# Driver_Motor.net
KiCad netlist of a schematic drawn in Altium Designer
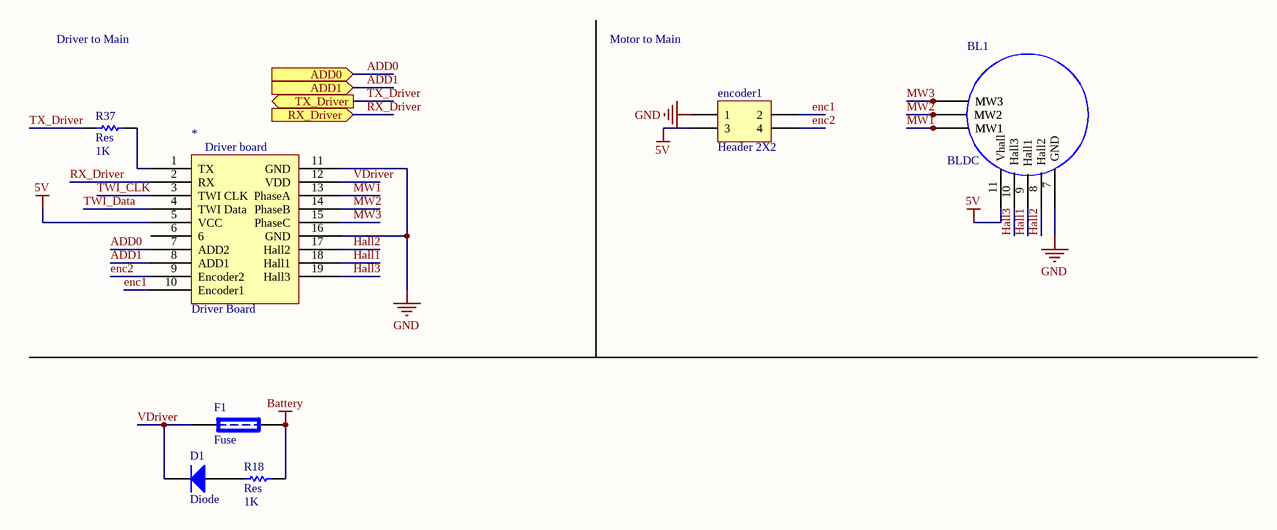
[diagram p0: Driver Motor.SchDoc]

(export (version "E")
  (design (tool "Eeschema 10.0.6"))
  (components
    (comp (ref "*")
      (value "Driver Board")
      (footprint "Driver board")
      (libsource (lib "KN2CLib") (part "Driver Board"))
    )
    (comp (ref "BL1") (value "BLDC") (footprint "FLT11") (libsource (lib "KN2CLib") (part "BLDC")))
    (comp (ref "D1")
      (value "Diode")
      (footprint "2012[0805]")
      (description "1 Amp General Purpose Rectifier")
      (fields (field (name "PUBLISHER") "Altium Limited"))
      (libsource (lib "KN2CLib") (part "Diode"))
    )
    (comp (ref "encoder1")
      (value "Header 2X2")
      (footprint "encoder 4pin")
      (description "Header, 2-Pin, Dual row")
      (fields (field (name "PUBLISHER") "Altium Limited"))
      (libsource (lib "Miscellaneous Connectors") (part "Header 2X2"))
    )
    (comp (ref "F1")
      (value "Fuse")
      (footprint "fuse kh")
      (fields (field (name "PUBLISHER") "Altium Limited"))
      (libsource (lib "KN2CLib") (part "Fuse"))
    )
    (comp (ref "R18")
      (value "Res")
      (footprint "2012[0805]")
      (description "Semiconductor Resistor")
      (fields (field (name "ALTIUM_VALUE") "1K") (field (name "PUBLISHER") "Altium Limited"))
      (libsource (lib "KN2CLib") (part "Res"))
    )
    (comp (ref "R37")
      (value "Res")
      (footprint "2012[0805]")
      (description "Semiconductor Resistor")
      (fields (field (name "ALTIUM_VALUE") "1K") (field (name "PUBLISHER") "Altium Limited"))
      (libsource (lib "KN2CLib") (part "Res"))
    )
  )
  (nets
    (net (code "1") (name "/ADD0") (class "Default")
      (node (ref "*") (pin "7") (pinfunction "ADD2_7") (pintype "passive"))
    )
    (net (code "2") (name "/ADD1") (class "Default")
      (node (ref "*") (pin "8") (pinfunction "ADD1_8") (pintype "passive"))
    )
    (net (code "3") (name "/Hall1") (class "Default")
      (node (ref "*") (pin "18") (pinfunction "Hall1_18") (pintype "passive"))
      (node (ref "BL1") (pin "9") (pinfunction "Hall1_9") (pintype "passive"))
    )
    (net (code "4") (name "/Hall2") (class "Default")
      (node (ref "*") (pin "17") (pinfunction "Hall2_17") (pintype "passive"))
      (node (ref "BL1") (pin "8") (pinfunction "Hall2_8") (pintype "passive"))
    )
    (net (code "5") (name "/Hall3") (class "Default")
      (node (ref "*") (pin "19") (pinfunction "Hall3_19") (pintype "passive"))
      (node (ref "BL1") (pin "10") (pinfunction "Hall3_10") (pintype "passive"))
    )
    (net (code "6") (name "/MW1") (class "Default")
      (node (ref "*") (pin "13") (pinfunction "PhaseA_13") (pintype "passive"))
      (node (ref "BL1") (pin "1") (pinfunction "MW1_1") (pintype "passive"))
      (node (ref "BL1") (pin "2") (pinfunction "MW1_2") (pintype "passive"))
    )
    (net (code "7") (name "/MW2") (class "Default")
      (node (ref "*") (pin "14") (pinfunction "PhaseB_14") (pintype "passive"))
      (node (ref "BL1") (pin "3") (pinfunction "MW2_3") (pintype "passive"))
      (node (ref "BL1") (pin "4") (pinfunction "MW2_4") (pintype "passive"))
    )
    (net (code "8") (name "/MW3") (class "Default")
      (node (ref "*") (pin "15") (pinfunction "PhaseC_15") (pintype "passive"))
      (node (ref "BL1") (pin "5") (pinfunction "MW3_5") (pintype "passive"))
      (node (ref "BL1") (pin "6") (pinfunction "MW3_6") (pintype "passive"))
    )
    (net (code "9") (name "/RX_Driver") (class "Default")
      (node (ref "*") (pin "2") (pinfunction "RX_2") (pintype "passive"))
    )
    (net (code "10") (name "/TWI_CLK") (class "Default")
      (node (ref "*") (pin "3") (pinfunction "TWI_CLK_3") (pintype "passive"))
    )
    (net (code "11") (name "/TWI_Data") (class "Default")
      (node (ref "*") (pin "4") (pinfunction "TWI_Data_4") (pintype "passive"))
    )
    (net (code "12") (name "/TX_Driver") (class "Default")
      (node (ref "R37") (pin "2") (pinfunction "2_2") (pintype "passive"))
    )
    (net (code "13") (name "/VDriver") (class "Default")
      (node (ref "*") (pin "12") (pinfunction "VDD_12") (pintype "passive"))
      (node (ref "D1") (pin "2") (pinfunction "K_2") (pintype "passive"))
      (node (ref "F1") (pin "1") (pinfunction "1_1") (pintype "passive"))
    )
    (net (code "14") (name "/enc1") (class "Default")
      (node (ref "*") (pin "10") (pinfunction "Encoder1_10") (pintype "passive"))
      (node (ref "encoder1") (pin "2") (pinfunction "2_2") (pintype "passive"))
    )
    (net (code "15") (name "/enc2") (class "Default")
      (node (ref "*") (pin "9") (pinfunction "Encoder2_9") (pintype "passive"))
      (node (ref "encoder1") (pin "4") (pinfunction "4_4") (pintype "passive"))
    )
    (net (code "16") (name "5V") (class "Default")
      (node (ref "*") (pin "5") (pinfunction "VCC_5") (pintype "passive"))
      (node (ref "BL1") (pin "11") (pinfunction "Vhall_11") (pintype "passive"))
      (node (ref "encoder1") (pin "3") (pinfunction "3_3") (pintype "passive"))
    )
    (net (code "17") (name "Battery") (class "Default")
      (node (ref "F1") (pin "2") (pinfunction "2_2") (pintype "passive"))
      (node (ref "R18") (pin "1") (pinfunction "1_1") (pintype "passive"))
    )
    (net (code "18") (name "GND") (class "Default")
      (node (ref "*") (pin "11") (pinfunction "GND_11") (pintype "passive"))
      (node (ref "*") (pin "16") (pinfunction "GND_16") (pintype "passive"))
      (node (ref "BL1") (pin "7") (pinfunction "GND_7") (pintype "passive"))
      (node (ref "encoder1") (pin "1") (pinfunction "1_1") (pintype "passive"))
    )
    (net (code "19") (name "Net-(*-TX)") (class "Default")
      (node (ref "*") (pin "1") (pinfunction "TX_1") (pintype "passive"))
      (node (ref "R37") (pin "1") (pinfunction "1_1") (pintype "passive"))
    )
    (net (code "20") (name "Net-(D1-A)") (class "Default")
      (node (ref "D1") (pin "1") (pinfunction "A_1") (pintype "passive"))
      (node (ref "R18") (pin "2") (pinfunction "2_2") (pintype "passive"))
    )
    (net (code "21") (name "unconnected-(*-Pad6)") (class "Default")
      (node (ref "*") (pin "6") (pinfunction "6_6") (pintype "passive"))
    )
  )
)
